# tvpong.net
KiCad netlist of a schematic drawn in EAGLE
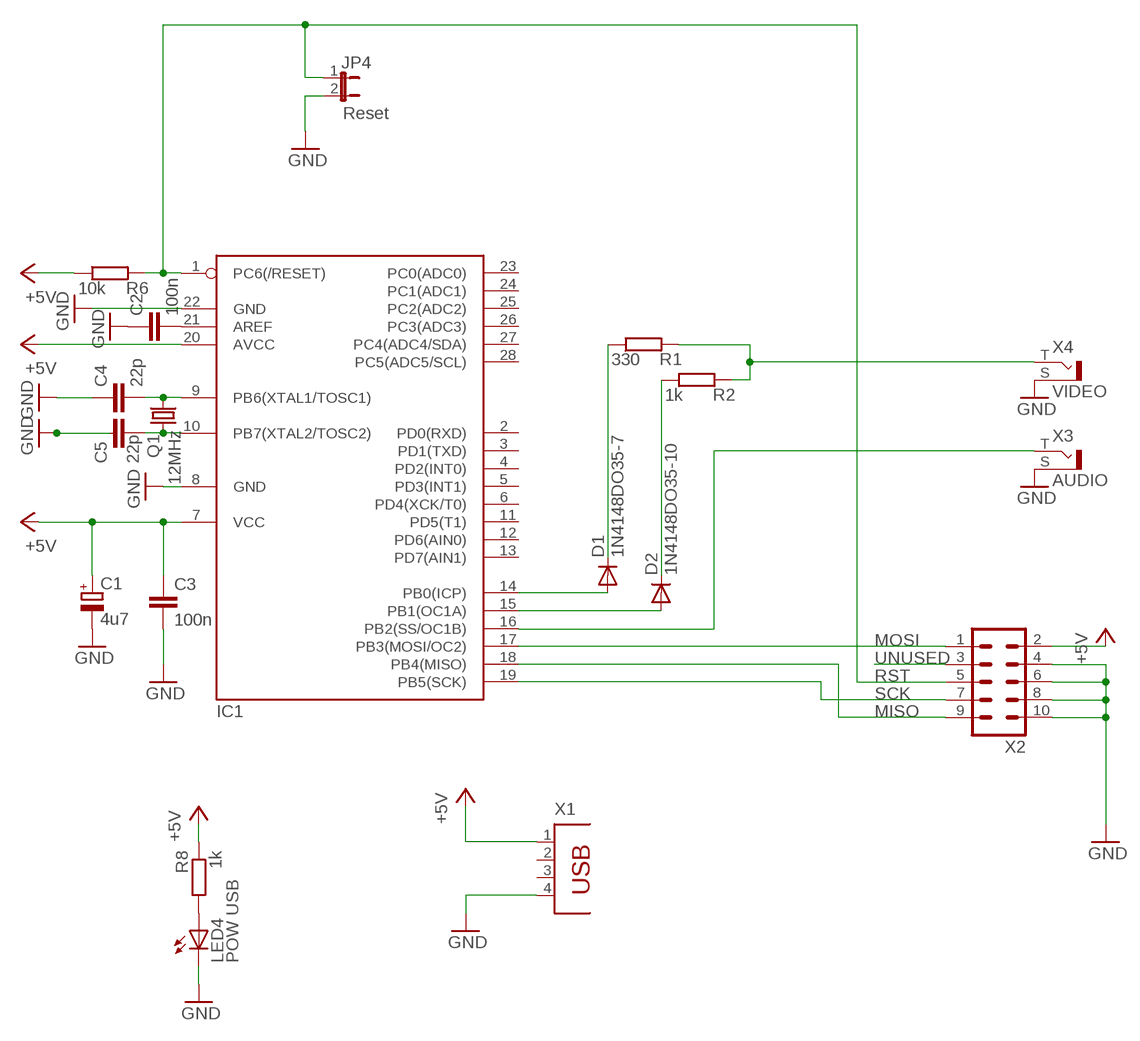
[diagram p0: schematic, sheet 1]

(export (version "E")
  (design (tool "Eeschema 10.0.6"))
  (components
    (comp (ref "C1")
      (value "4u7")
      (footprint "eagle-import:TT2D5")
      (libsource (lib "eagle-import") (part "CPOL-EUTT2D5"))
    )
    (comp (ref "C2")
      (value "100n")
      (footprint "eagle-import:C025-024X044")
      (libsource (lib "eagle-import") (part "C-EU025-024X044"))
    )
    (comp (ref "C3")
      (value "100n")
      (footprint "eagle-import:C025-024X044")
      (libsource (lib "eagle-import") (part "C-EU025-024X044"))
    )
    (comp (ref "C4")
      (value "22p")
      (footprint "eagle-import:C025-024X044")
      (libsource (lib "eagle-import") (part "C-EU025-024X044"))
    )
    (comp (ref "C5")
      (value "22p")
      (footprint "eagle-import:C050-025X075")
      (libsource (lib "eagle-import") (part "C-EU050-025X075"))
    )
    (comp (ref "D1")
      (value "1N4148DO35-7")
      (footprint "eagle-import:DO35-7")
      (libsource (lib "eagle-import") (part "1N4148DO35-7"))
    )
    (comp (ref "D2")
      (value "1N4148DO35-10")
      (footprint "eagle-import:DO35-10")
      (libsource (lib "eagle-import") (part "1N4148DO35-10"))
    )
    (comp (ref "IC1")
      (value "MEGA8-P")
      (footprint "eagle-import:DIL28-3")
      (libsource (lib "eagle-import") (part "MEGA8-P"))
    )
    (comp (ref "JP4")
      (value "Reset")
      (footprint "eagle-import:JP1")
      (libsource (lib "eagle-import") (part "JP1E"))
    )
    (comp (ref "LED4")
      (value "POW USB")
      (footprint "eagle-import:LED3MM")
      (libsource (lib "eagle-import") (part "LED3MM"))
    )
    (comp (ref "Q1")
      (value "12MHz")
      (footprint "eagle-import:TC26V")
      (libsource (lib "eagle-import") (part "CRYSTALTC26V"))
    )
    (comp (ref "R1")
      (value "330")
      (footprint "eagle-import:0207_12")
      (libsource (lib "eagle-import") (part "R-EU_0207/12"))
    )
    (comp (ref "R2")
      (value "1k")
      (footprint "eagle-import:0207_15")
      (libsource (lib "eagle-import") (part "R-EU_0207/15"))
    )
    (comp (ref "R6")
      (value "10k")
      (footprint "eagle-import:0207_15")
      (libsource (lib "eagle-import") (part "R-EU_0207/15"))
    )
    (comp (ref "R8")
      (value "1k")
      (footprint "eagle-import:0204_5")
      (libsource (lib "eagle-import") (part "R-EU_0204/5"))
    )
    (comp (ref "X1")
      (value "PN61729")
      (footprint "eagle-import:PN61729")
      (libsource (lib "eagle-import") (part "PN61729"))
    )
    (comp (ref "X2")
      (value "ML10L")
      (footprint "eagle-import:ML10L")
      (libsource (lib "eagle-import") (part "ML10L"))
    )
    (comp (ref "X3")
      (value "AUDIO")
      (footprint "eagle-import:WBTOR1")
      (fields (field (name "MPN") "WBTOR 1 BLACK"))
      (libsource (lib "eagle-import") (part "WBTOR1"))
    )
    (comp (ref "X4")
      (value "VIDEO")
      (footprint "eagle-import:WBTOR1")
      (fields (field (name "MPN") "WBTOR 1 BLACK"))
      (libsource (lib "eagle-import") (part "WBTOR1"))
    )
  )
  (nets
    (net (code "1") (name "+5V") (class "Default")
      (node (ref "C1") (pin "+") (pinfunction "+_+") (pintype "passive"))
      (node (ref "C3") (pin "1") (pinfunction "1_1") (pintype "passive"))
      (node (ref "IC1") (pin "20") (pinfunction "AVCC_20") (pintype "power_in"))
      (node (ref "IC1") (pin "7") (pinfunction "VCC_7") (pintype "power_in"))
      (node (ref "R6") (pin "1") (pinfunction "1_1") (pintype "passive"))
      (node (ref "R8") (pin "1") (pinfunction "1_1") (pintype "passive"))
      (node (ref "X1") (pin "1") (pinfunction "1_1") (pintype "passive"))
      (node (ref "X2") (pin "2") (pinfunction "2_2") (pintype "passive"))
    )
    (net (code "2") (name "/MISO") (class "Default")
      (node (ref "IC1") (pin "18") (pinfunction "PB4(MISO)_18") (pintype "bidirectional"))
      (node (ref "X2") (pin "9") (pinfunction "9_9") (pintype "passive"))
    )
    (net (code "3") (name "/MOSI") (class "Default")
      (node (ref "IC1") (pin "17") (pinfunction "PB3(MOSI/OC2)_17") (pintype "bidirectional"))
      (node (ref "X2") (pin "1") (pinfunction "1_1") (pintype "passive"))
    )
    (net (code "4") (name "/RST") (class "Default")
      (node (ref "IC1") (pin "1") (pinfunction "PC6(/RESET)_1") (pintype "bidirectional"))
      (node (ref "JP4") (pin "1") (pinfunction "1_1") (pintype "passive"))
      (node (ref "R6") (pin "2") (pinfunction "2_2") (pintype "passive"))
      (node (ref "X2") (pin "5") (pinfunction "5_5") (pintype "passive"))
    )
    (net (code "5") (name "/SCK") (class "Default")
      (node (ref "IC1") (pin "19") (pinfunction "PB5(SCK)_19") (pintype "bidirectional"))
      (node (ref "X2") (pin "7") (pinfunction "7_7") (pintype "passive"))
    )
    (net (code "6") (name "/UNUSED") (class "Default")
      (node (ref "X2") (pin "3") (pinfunction "3_3") (pintype "passive"))
    )
    (net (code "7") (name "GND") (class "Default")
      (node (ref "C1") (pin "-") (pinfunction "-_-") (pintype "passive"))
      (node (ref "C2") (pin "1") (pinfunction "1_1") (pintype "passive"))
      (node (ref "C3") (pin "2") (pinfunction "2_2") (pintype "passive"))
      (node (ref "C4") (pin "1") (pinfunction "1_1") (pintype "passive"))
      (node (ref "C5") (pin "1") (pinfunction "1_1") (pintype "passive"))
      (node (ref "IC1") (pin "22") (pinfunction "GND_22") (pintype "power_in"))
      (node (ref "IC1") (pin "8") (pinfunction "GND_8") (pintype "power_in"))
      (node (ref "JP4") (pin "2") (pinfunction "2_2") (pintype "passive"))
      (node (ref "LED4") (pin "K") (pinfunction "C_K") (pintype "passive"))
      (node (ref "X1") (pin "4") (pinfunction "4_4") (pintype "passive"))
      (node (ref "X2") (pin "10") (pinfunction "10_10") (pintype "passive"))
      (node (ref "X2") (pin "4") (pinfunction "4_4") (pintype "passive"))
      (node (ref "X2") (pin "6") (pinfunction "6_6") (pintype "passive"))
      (node (ref "X2") (pin "8") (pinfunction "8_8") (pintype "passive"))
      (node (ref "X3") (pin "S") (pinfunction "S_S") (pintype "passive"))
      (node (ref "X4") (pin "S") (pinfunction "S_S") (pintype "passive"))
    )
    (net (code "8") (name "Net-(D1-PadC)") (class "Default")
      (node (ref "D1") (pin "C") (pinfunction "C_C") (pintype "passive"))
      (node (ref "R1") (pin "1") (pinfunction "1_1") (pintype "passive"))
    )
    (net (code "9") (name "Net-(D2-PadC)") (class "Default")
      (node (ref "D2") (pin "C") (pinfunction "C_C") (pintype "passive"))
      (node (ref "R2") (pin "1") (pinfunction "1_1") (pintype "passive"))
    )
    (net (code "10") (name "Net-(IC1-AREF)") (class "Default")
      (node (ref "C2") (pin "2") (pinfunction "2_2") (pintype "passive"))
      (node (ref "IC1") (pin "21") (pinfunction "AREF_21") (pintype "passive"))
    )
    (net (code "11") (name "Net-(IC1-PB0(ICP))") (class "Default")
      (node (ref "D1") (pin "A") (pinfunction "A_A") (pintype "passive"))
      (node (ref "IC1") (pin "14") (pinfunction "PB0(ICP)_14") (pintype "bidirectional"))
    )
    (net (code "12") (name "Net-(IC1-PB1(OC1A))") (class "Default")
      (node (ref "D2") (pin "A") (pinfunction "A_A") (pintype "passive"))
      (node (ref "IC1") (pin "15") (pinfunction "PB1(OC1A)_15") (pintype "bidirectional"))
    )
    (net (code "13") (name "Net-(IC1-PB2(SS{slash}OC1B))") (class "Default")
      (node (ref "IC1") (pin "16") (pinfunction "PB2(SS/OC1B)_16") (pintype "bidirectional"))
      (node (ref "X3") (pin "T") (pinfunction "T_T") (pintype "passive"))
    )
    (net (code "14") (name "Net-(IC1-PB6(XTAL1{slash}TOSC1))") (class "Default")
      (node (ref "C4") (pin "2") (pinfunction "2_2") (pintype "passive"))
      (node (ref "IC1") (pin "9") (pinfunction "PB6(XTAL1/TOSC1)_9") (pintype "bidirectional"))
      (node (ref "Q1") (pin "2") (pinfunction "2_2") (pintype "passive"))
    )
    (net (code "15") (name "Net-(IC1-PB7(XTAL2{slash}TOSC2))") (class "Default")
      (node (ref "C5") (pin "2") (pinfunction "2_2") (pintype "passive"))
      (node (ref "IC1") (pin "10") (pinfunction "PB7(XTAL2/TOSC2)_10") (pintype "bidirectional"))
      (node (ref "Q1") (pin "1") (pinfunction "1_1") (pintype "passive"))
    )
    (net (code "16") (name "Net-(LED4-PadA)") (class "Default")
      (node (ref "LED4") (pin "A") (pinfunction "A_A") (pintype "passive"))
      (node (ref "R8") (pin "2") (pinfunction "2_2") (pintype "passive"))
    )
    (net (code "17") (name "Net-(R1-Pad2)") (class "Default")
      (node (ref "R1") (pin "2") (pinfunction "2_2") (pintype "passive"))
      (node (ref "R2") (pin "2") (pinfunction "2_2") (pintype "passive"))
      (node (ref "X4") (pin "T") (pinfunction "T_T") (pintype "passive"))
    )
    (net (code "18") (name "unconnected-(IC1-PC0(ADC0)-Pad23)") (class "Default")
      (node (ref "IC1") (pin "23") (pinfunction "PC0(ADC0)_23") (pintype "bidirectional"))
    )
    (net (code "19") (name "unconnected-(IC1-PC1(ADC1)-Pad24)") (class "Default")
      (node (ref "IC1") (pin "24") (pinfunction "PC1(ADC1)_24") (pintype "bidirectional"))
    )
    (net (code "20") (name "unconnected-(IC1-PC2(ADC2)-Pad25)") (class "Default")
      (node (ref "IC1") (pin "25") (pinfunction "PC2(ADC2)_25") (pintype "bidirectional"))
    )
    (net (code "21") (name "unconnected-(IC1-PC3(ADC3)-Pad26)") (class "Default")
      (node (ref "IC1") (pin "26") (pinfunction "PC3(ADC3)_26") (pintype "bidirectional"))
    )
    (net (code "22") (name "unconnected-(IC1-PC4(ADC4{slash}SDA)-Pad27)") (class "Default")
      (node (ref "IC1") (pin "27") (pinfunction "PC4(ADC4/SDA)_27") (pintype "bidirectional"))
    )
    (net (code "23") (name "unconnected-(IC1-PC5(ADC5{slash}SCL)-Pad28)") (class "Default")
      (node (ref "IC1") (pin "28") (pinfunction "PC5(ADC5/SCL)_28") (pintype "bidirectional"))
    )
    (net (code "24") (name "unconnected-(IC1-PD0(RXD)-Pad2)") (class "Default")
      (node (ref "IC1") (pin "2") (pinfunction "PD0(RXD)_2") (pintype "bidirectional"))
    )
    (net (code "25") (name "unconnected-(IC1-PD1(TXD)-Pad3)") (class "Default")
      (node (ref "IC1") (pin "3") (pinfunction "PD1(TXD)_3") (pintype "bidirectional"))
    )
    (net (code "26") (name "unconnected-(IC1-PD2(INT0)-Pad4)") (class "Default")
      (node (ref "IC1") (pin "4") (pinfunction "PD2(INT0)_4") (pintype "bidirectional"))
    )
    (net (code "27") (name "unconnected-(IC1-PD3(INT1)-Pad5)") (class "Default")
      (node (ref "IC1") (pin "5") (pinfunction "PD3(INT1)_5") (pintype "bidirectional"))
    )
    (net (code "28") (name "unconnected-(IC1-PD4(XCK{slash}T0)-Pad6)") (class "Default")
      (node (ref "IC1") (pin "6") (pinfunction "PD4(XCK/T0)_6") (pintype "bidirectional"))
    )
    (net (code "29") (name "unconnected-(IC1-PD5(T1)-Pad11)") (class "Default")
      (node (ref "IC1") (pin "11") (pinfunction "PD5(T1)_11") (pintype "bidirectional"))
    )
    (net (code "30") (name "unconnected-(IC1-PD6(AIN0)-Pad12)") (class "Default")
      (node (ref "IC1") (pin "12") (pinfunction "PD6(AIN0)_12") (pintype "bidirectional"))
    )
    (net (code "31") (name "unconnected-(IC1-PD7(AIN1)-Pad13)") (class "Default")
      (node (ref "IC1") (pin "13") (pinfunction "PD7(AIN1)_13") (pintype "bidirectional"))
    )
    (net (code "32") (name "unconnected-(X1-Pad2)") (class "Default")
      (node (ref "X1") (pin "2") (pinfunction "2_2") (pintype "passive"))
    )
    (net (code "33") (name "unconnected-(X1-Pad3)") (class "Default")
      (node (ref "X1") (pin "3") (pinfunction "3_3") (pintype "passive"))
    )
  )
)
